# CPLD.net
KiCad netlist of a schematic drawn in Altium Designer
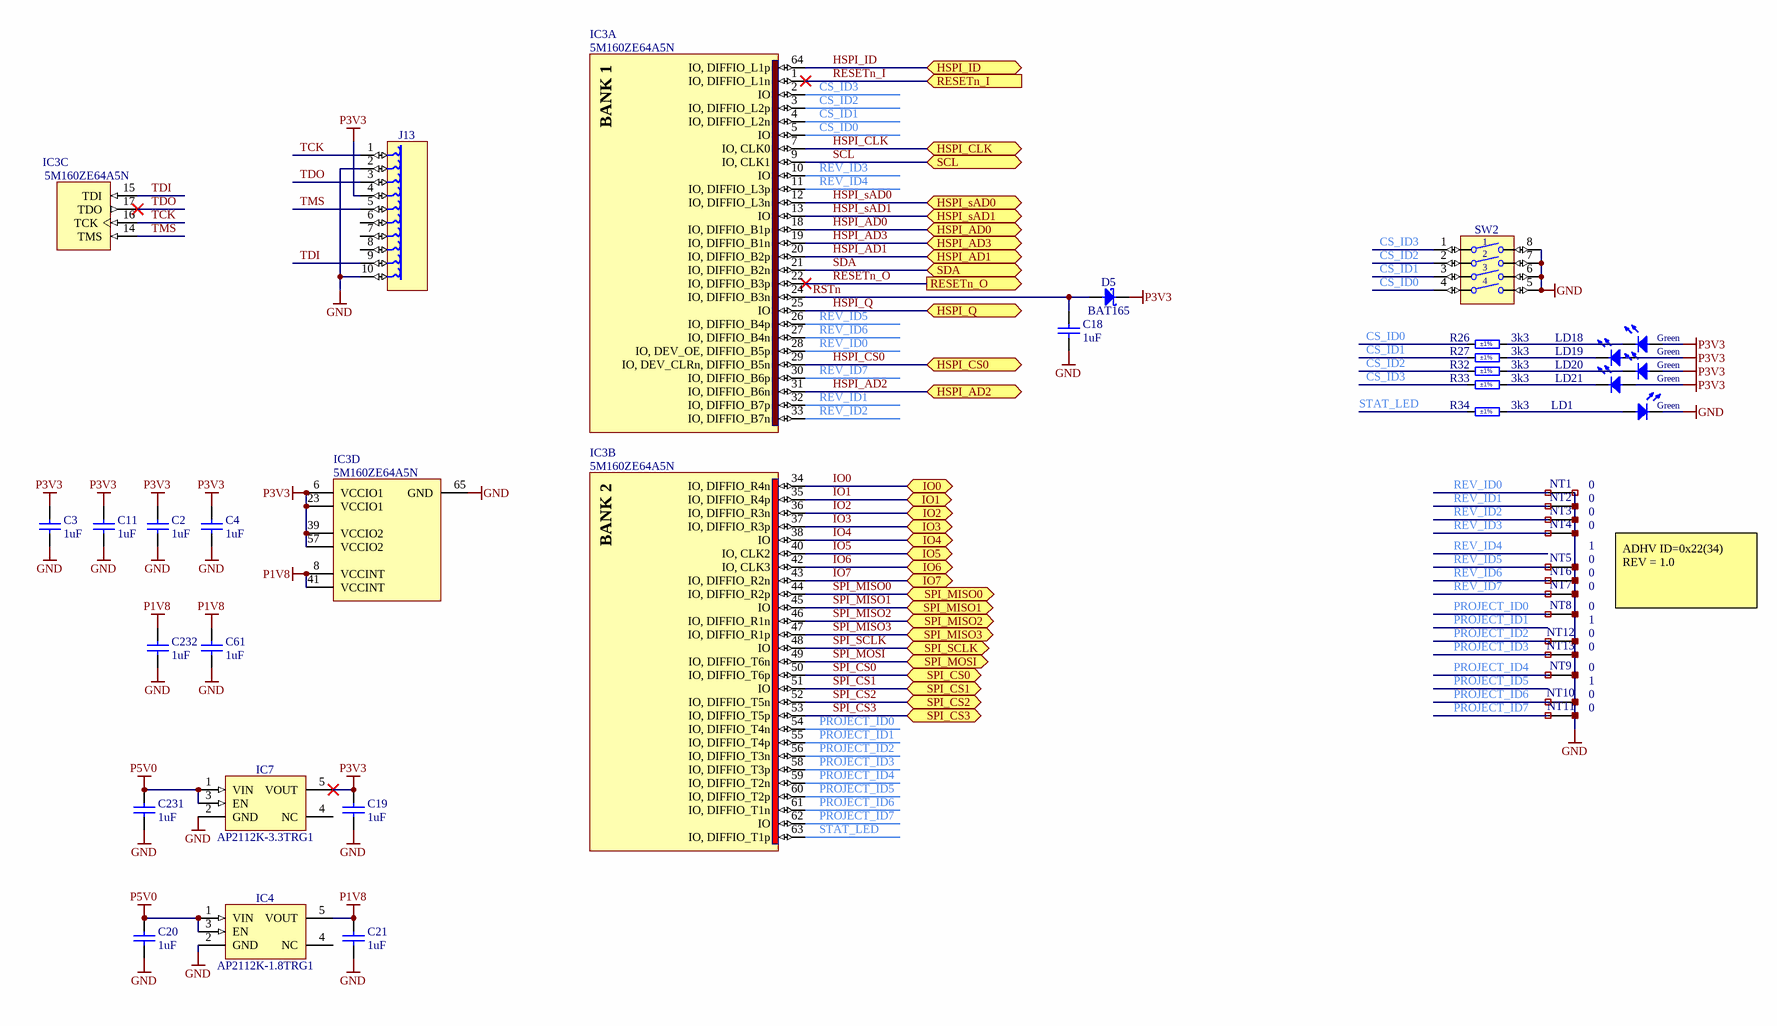
[diagram p0: CPLD.SchDoc]

(export (version "E")
  (design (tool "Eeschema 10.0.6"))
  (components
    (comp (ref "C2")
      (value "1uF")
      (footprint "CAPC1005X55N")
      (description "Non-polarised capacitor")
      (fields
        (field (name "PART NUMBER") "CC0402_1UF_16V_10%_X5R")
        (field (name "VOLTAGE") "16V")
        (field (name "AUTHOR") "CERN DEM JLC")
      )
      (libsource (lib "Capacitors") (part "Capacitor - non polarized"))
    )
    (comp (ref "C3")
      (value "1uF")
      (footprint "CAPC1005X55N")
      (description "Non-polarised capacitor")
      (fields
        (field (name "PART NUMBER") "CC0402_1UF_16V_10%_X5R")
        (field (name "VOLTAGE") "16V")
        (field (name "AUTHOR") "CERN DEM JLC")
      )
      (libsource (lib "Capacitors") (part "Capacitor - non polarized"))
    )
    (comp (ref "C4")
      (value "1uF")
      (footprint "CAPC1005X55N")
      (description "Non-polarised capacitor")
      (fields
        (field (name "PART NUMBER") "CC0402_1UF_16V_10%_X5R")
        (field (name "VOLTAGE") "16V")
        (field (name "AUTHOR") "CERN DEM JLC")
      )
      (libsource (lib "Capacitors") (part "Capacitor - non polarized"))
    )
    (comp (ref "C11")
      (value "1uF")
      (footprint "CAPC1005X55N")
      (description "Non-polarised capacitor")
      (fields
        (field (name "PART NUMBER") "CC0402_1UF_16V_10%_X5R")
        (field (name "VOLTAGE") "16V")
        (field (name "AUTHOR") "CERN DEM JLC")
      )
      (libsource (lib "Capacitors") (part "Capacitor - non polarized"))
    )
    (comp (ref "C18")
      (value "1uF")
      (footprint "CAPC1005X55N")
      (description "Non-polarised capacitor")
      (fields
        (field (name "PART NUMBER") "CC0402_1UF_16V_10%_X5R")
        (field (name "VOLTAGE") "16V")
        (field (name "AUTHOR") "CERN DEM JLC")
      )
      (libsource (lib "Capacitors") (part "Capacitor - non polarized"))
    )
    (comp (ref "C19")
      (value "1uF")
      (footprint "CAPC1005X55N")
      (description "Non-polarised capacitor")
      (fields
        (field (name "PART NUMBER") "CC0402_1UF_16V_10%_X5R")
        (field (name "VOLTAGE") "16V")
        (field (name "AUTHOR") "CERN DEM JLC")
      )
      (libsource (lib "Capacitors") (part "Capacitor - non polarized"))
    )
    (comp (ref "C20")
      (value "1uF")
      (footprint "CAPC1005X55N")
      (description "Non-polarised capacitor")
      (fields
        (field (name "PART NUMBER") "CC0402_1UF_16V_10%_X5R")
        (field (name "VOLTAGE") "16V")
        (field (name "AUTHOR") "CERN DEM JLC")
      )
      (libsource (lib "Capacitors") (part "Capacitor - non polarized"))
    )
    (comp (ref "C21")
      (value "1uF")
      (footprint "CAPC1005X55N")
      (description "Non-polarised capacitor")
      (fields
        (field (name "PART NUMBER") "CC0402_1UF_16V_10%_X5R")
        (field (name "VOLTAGE") "16V")
        (field (name "AUTHOR") "CERN DEM JLC")
      )
      (libsource (lib "Capacitors") (part "Capacitor - non polarized"))
    )
    (comp (ref "C61")
      (value "1uF")
      (footprint "CAPC1005X55N")
      (description "Non-polarised capacitor")
      (fields
        (field (name "PART NUMBER") "CC0402_1UF_16V_10%_X5R")
        (field (name "VOLTAGE") "16V")
        (field (name "AUTHOR") "CERN DEM JLC")
      )
      (libsource (lib "Capacitors") (part "Capacitor - non polarized"))
    )
    (comp (ref "C231")
      (value "1uF")
      (footprint "CAPC1005X55N")
      (description "Non-polarised capacitor")
      (fields
        (field (name "PART NUMBER") "CC0402_1UF_16V_10%_X5R")
        (field (name "VOLTAGE") "16V")
        (field (name "AUTHOR") "CERN DEM JLC")
      )
      (libsource (lib "Capacitors") (part "Capacitor - non polarized"))
    )
    (comp (ref "C232")
      (value "1uF")
      (footprint "CAPC1005X55N")
      (description "Non-polarised capacitor")
      (fields
        (field (name "PART NUMBER") "CC0402_1UF_16V_10%_X5R")
        (field (name "VOLTAGE") "16V")
        (field (name "AUTHOR") "CERN DEM JLC")
      )
      (libsource (lib "Capacitors") (part "Capacitor - non polarized"))
    )
    (comp (ref "D5")
      (value "BAT165")
      (footprint "SOD2512X110N")
      (description "Schottky Diode")
      (fields
        (field (name "VOLTAGE") "40V")
        (field (name "POWER") "750mA")
        (field (name "AUTHOR") "CERN DEM JLC")
      )
      (libsource (lib "ICs And Semiconductors") (part "Diode Schottky"))
    )
    (comp (ref "IC3")
      (value "5M160ZE64A5N")
      (footprint "QFP40P900X900X120-65N-S550")
      (fields (field (name "MANUFACTURER") "ALTERA") (field (name "AUTHOR") "CERN DEM JLC"))
      (libsource (lib "") (part "5M160ZE64A5N_1"))
    )
    (comp (ref "IC4")
      (value "AP2112K-1.8TRG1")
      (footprint "SOT95P285X140-5N")
      (description "600mA CMOS Low Dropout Linear Regulator with Enable")
      (fields
        (field (name "MANUFACTURER") "DIODES INCORPORATED")
        (field (name "MANUFACTURER PART NUMBER") "AP2112K-1.8")
        (field (name "AUTHOR") "CERN DEM JLC")
      )
      (libsource (lib "ICs And Semiconductors") (part "AP2112K"))
    )
    (comp (ref "IC7")
      (value "AP2112K-3.3TRG1")
      (footprint "SOT95P285X140-5N")
      (description "600mA CMOS Low Dropout Linear Regulator with Enable")
      (fields
        (field (name "MANUFACTURER") "DIODES INCORPORATED")
        (field (name "MANUFACTURER PART NUMBER") "AP2112K-3.3")
        (field (name "AUTHOR") "CERN DEM MR")
      )
      (libsource (lib "ICs And Semiconductors") (part "AP2112K"))
    )
    (comp (ref "J13")
      (value "TC2050-IDC")
      (footprint "TC2050-IDC")
      (description "TC2030-MCP and TC2050-IDC Pad Contact")
      (fields (field (name "AUTHOR") "CERN DEM HF"))
      (libsource (lib "Eletro-mechanical") (part "TC2050-IDC"))
    )
    (comp (ref "LD1")
      (value "Green")
      (footprint "LED_KINGBRIGHT_KP-1608CGCK")
      (description "LED Green 1C 2A")
      (fields
        (field (name "PART NUMBER") "LED_KINGBRIGHT_KP-1608CGCK")
        (field (name "MANUFACTURER") "KINGBRIGHT")
        (field (name "AUTHOR") "CERN DEM HF")
      )
      (libsource (lib "ICs And Semiconductors") (part "LED Green 1C 2A"))
    )
    (comp (ref "LD18")
      (value "Green")
      (footprint "LED_KINGBRIGHT_KP-1608CGCK")
      (description "LED Green 1C 2A")
      (fields
        (field (name "PART NUMBER") "LED_KINGBRIGHT_KP-1608CGCK")
        (field (name "MANUFACTURER") "KINGBRIGHT")
        (field (name "AUTHOR") "CERN DEM HF")
      )
      (libsource (lib "ICs And Semiconductors") (part "LED Green 1C 2A"))
    )
    (comp (ref "LD19")
      (value "Green")
      (footprint "LED_KINGBRIGHT_KP-1608CGCK")
      (description "LED Green 1C 2A")
      (fields
        (field (name "PART NUMBER") "LED_KINGBRIGHT_KP-1608CGCK")
        (field (name "MANUFACTURER") "KINGBRIGHT")
        (field (name "AUTHOR") "CERN DEM HF")
      )
      (libsource (lib "ICs And Semiconductors") (part "LED Green 1C 2A"))
    )
    (comp (ref "LD20")
      (value "Green")
      (footprint "LED_KINGBRIGHT_KP-1608CGCK")
      (description "LED Green 1C 2A")
      (fields
        (field (name "PART NUMBER") "LED_KINGBRIGHT_KP-1608CGCK")
        (field (name "MANUFACTURER") "KINGBRIGHT")
        (field (name "AUTHOR") "CERN DEM HF")
      )
      (libsource (lib "ICs And Semiconductors") (part "LED Green 1C 2A"))
    )
    (comp (ref "LD21")
      (value "Green")
      (footprint "LED_KINGBRIGHT_KP-1608CGCK")
      (description "LED Green 1C 2A")
      (fields
        (field (name "PART NUMBER") "LED_KINGBRIGHT_KP-1608CGCK")
        (field (name "MANUFACTURER") "KINGBRIGHT")
        (field (name "AUTHOR") "CERN DEM HF")
      )
      (libsource (lib "ICs And Semiconductors") (part "LED Green 1C 2A"))
    )
    (comp (ref "NT1")
      (value "Net Tie")
      (footprint "Net Tie 3")
      (fields (field (name "PART NUMBER") "Net Tie 3") (field (name "AUTHOR") "CERN DEM HF"))
      (libsource (lib "Eletro-mechanical") (part "Net Tie_a"))
    )
    (comp (ref "NT2")
      (value "Net Tie")
      (footprint "Net Tie 3")
      (fields (field (name "PART NUMBER") "Net Tie 3") (field (name "AUTHOR") "CERN DEM HF"))
      (libsource (lib "Eletro-mechanical") (part "Net Tie_a"))
    )
    (comp (ref "NT3")
      (value "Net Tie")
      (footprint "Net Tie 3")
      (fields (field (name "PART NUMBER") "Net Tie 3") (field (name "AUTHOR") "CERN DEM HF"))
      (libsource (lib "Eletro-mechanical") (part "Net Tie_a"))
    )
    (comp (ref "NT4")
      (value "Net Tie")
      (footprint "Net Tie 3")
      (fields (field (name "PART NUMBER") "Net Tie 3") (field (name "AUTHOR") "CERN DEM HF"))
      (libsource (lib "Eletro-mechanical") (part "Net Tie_a"))
    )
    (comp (ref "NT5")
      (value "Net Tie")
      (footprint "Net Tie 3")
      (fields (field (name "PART NUMBER") "Net Tie 3") (field (name "AUTHOR") "CERN DEM HF"))
      (libsource (lib "Eletro-mechanical") (part "Net Tie_a"))
    )
    (comp (ref "NT6")
      (value "Net Tie")
      (footprint "Net Tie 3")
      (fields (field (name "PART NUMBER") "Net Tie 3") (field (name "AUTHOR") "CERN DEM HF"))
      (libsource (lib "Eletro-mechanical") (part "Net Tie_a"))
    )
    (comp (ref "NT7")
      (value "Net Tie")
      (footprint "Net Tie 3")
      (fields (field (name "PART NUMBER") "Net Tie 3") (field (name "AUTHOR") "CERN DEM HF"))
      (libsource (lib "Eletro-mechanical") (part "Net Tie_a"))
    )
    (comp (ref "NT8")
      (value "Net Tie")
      (footprint "Net Tie 3")
      (fields (field (name "PART NUMBER") "Net Tie 3") (field (name "AUTHOR") "CERN DEM HF"))
      (libsource (lib "Eletro-mechanical") (part "Net Tie_a"))
    )
    (comp (ref "NT9")
      (value "Net Tie")
      (footprint "Net Tie 3")
      (fields (field (name "PART NUMBER") "Net Tie 3") (field (name "AUTHOR") "CERN DEM HF"))
      (libsource (lib "Eletro-mechanical") (part "Net Tie_a"))
    )
    (comp (ref "NT10")
      (value "Net Tie")
      (footprint "Net Tie 3")
      (fields (field (name "PART NUMBER") "Net Tie 3") (field (name "AUTHOR") "CERN DEM HF"))
      (libsource (lib "Eletro-mechanical") (part "Net Tie_a"))
    )
    (comp (ref "NT11")
      (value "Net Tie")
      (footprint "Net Tie 3")
      (fields (field (name "PART NUMBER") "Net Tie 3") (field (name "AUTHOR") "CERN DEM HF"))
      (libsource (lib "Eletro-mechanical") (part "Net Tie_a"))
    )
    (comp (ref "NT12")
      (value "Net Tie")
      (footprint "Net Tie 3")
      (fields (field (name "PART NUMBER") "Net Tie 3") (field (name "AUTHOR") "CERN DEM HF"))
      (libsource (lib "Eletro-mechanical") (part "Net Tie_a"))
    )
    (comp (ref "NT13")
      (value "Net Tie")
      (footprint "Net Tie 3")
      (fields (field (name "PART NUMBER") "Net Tie 3") (field (name "AUTHOR") "CERN DEM HF"))
      (libsource (lib "Eletro-mechanical") (part "Net Tie_a"))
    )
    (comp (ref "R26")
      (value "3k3")
      (footprint "RESC1005X40N")
      (description "Resistor - 1%")
      (fields
        (field (name "TOLERANCE") "±1%")
        (field (name "PART NUMBER") "R0402_3K3_1%_0.0625W_100PPM")
        (field (name "POWER") "0.0625W")
        (field (name "AUTHOR") "CERN DEM JLC")
      )
      (libsource (lib "Resistors") (part "Resistor - 1%"))
    )
    (comp (ref "R27")
      (value "3k3")
      (footprint "RESC1005X40N")
      (description "Resistor - 1%")
      (fields
        (field (name "TOLERANCE") "±1%")
        (field (name "PART NUMBER") "R0402_3K3_1%_0.0625W_100PPM")
        (field (name "POWER") "0.0625W")
        (field (name "AUTHOR") "CERN DEM JLC")
      )
      (libsource (lib "Resistors") (part "Resistor - 1%"))
    )
    (comp (ref "R32")
      (value "3k3")
      (footprint "RESC1005X40N")
      (description "Resistor - 1%")
      (fields
        (field (name "TOLERANCE") "±1%")
        (field (name "PART NUMBER") "R0402_3K3_1%_0.0625W_100PPM")
        (field (name "POWER") "0.0625W")
        (field (name "AUTHOR") "CERN DEM JLC")
      )
      (libsource (lib "Resistors") (part "Resistor - 1%"))
    )
    (comp (ref "R33")
      (value "3k3")
      (footprint "RESC1005X40N")
      (description "Resistor - 1%")
      (fields
        (field (name "TOLERANCE") "±1%")
        (field (name "PART NUMBER") "R0402_3K3_1%_0.0625W_100PPM")
        (field (name "POWER") "0.0625W")
        (field (name "AUTHOR") "CERN DEM JLC")
      )
      (libsource (lib "Resistors") (part "Resistor - 1%"))
    )
    (comp (ref "R34")
      (value "3k3")
      (footprint "RESC1005X40N")
      (description "Resistor - 1%")
      (fields
        (field (name "TOLERANCE") "±1%")
        (field (name "PART NUMBER") "R0402_3K3_1%_0.0625W_100PPM")
        (field (name "POWER") "0.0625W")
        (field (name "AUTHOR") "CERN DEM JLC")
      )
      (libsource (lib "Resistors") (part "Resistor - 1%"))
    )
    (comp (ref "SW2")
      (value "Switch")
      (footprint "SW_OMRON_A6H-4102")
      (description "4 Ways SPST DIP Switch")
      (fields
        (field (name "PART NUMBER") "SW_OMRON_A6H-4102")
        (field (name "MANUFACTURER") "OMRON")
        (field (name "AUTHOR") "CERN DEM JLC")
      )
      (libsource (lib "Eletro-mechanical") (part "SW 4x SPST DIP Switch"))
    )
  )
  (nets
    (net (code "1") (name "/CS_ID0") (class "Default")
      (node (ref "IC3") (pin "5") (pinfunction "IO_5") (pintype "bidirectional"))
      (node (ref "R26") (pin "2") (pinfunction "2_2") (pintype "passive"))
      (node (ref "SW2") (pin "4") (pinfunction "4_4") (pintype "bidirectional"))
    )
    (net (code "2") (name "/CS_ID1") (class "Default")
      (node (ref "IC3") (pin "4") (pinfunction "IO,_DIFFIO_L2n_4") (pintype "bidirectional"))
      (node (ref "R27") (pin "2") (pinfunction "2_2") (pintype "passive"))
      (node (ref "SW2") (pin "3") (pinfunction "3_3") (pintype "bidirectional"))
    )
    (net (code "3") (name "/CS_ID2") (class "Default")
      (node (ref "IC3") (pin "3") (pinfunction "IO,_DIFFIO_L2p_3") (pintype "bidirectional"))
      (node (ref "R32") (pin "2") (pinfunction "2_2") (pintype "passive"))
      (node (ref "SW2") (pin "2") (pinfunction "2_2") (pintype "bidirectional"))
    )
    (net (code "4") (name "/CS_ID3") (class "Default")
      (node (ref "IC3") (pin "2") (pinfunction "IO_2") (pintype "bidirectional"))
      (node (ref "R33") (pin "2") (pinfunction "2_2") (pintype "passive"))
      (node (ref "SW2") (pin "1") (pinfunction "1_1") (pintype "bidirectional"))
    )
    (net (code "5") (name "/HSPI_AD0") (class "Default")
      (node (ref "IC3") (pin "18") (pinfunction "IO,_DIFFIO_B1p_18") (pintype "bidirectional"))
    )
    (net (code "6") (name "/HSPI_AD1") (class "Default")
      (node (ref "IC3") (pin "20") (pinfunction "IO,_DIFFIO_B2p_20") (pintype "bidirectional"))
    )
    (net (code "7") (name "/HSPI_AD2") (class "Default")
      (node (ref "IC3") (pin "31") (pinfunction "IO,_DIFFIO_B6n_31") (pintype "bidirectional"))
    )
    (net (code "8") (name "/HSPI_AD3") (class "Default")
      (node (ref "IC3") (pin "19") (pinfunction "IO,_DIFFIO_B1n_19") (pintype "bidirectional"))
    )
    (net (code "9") (name "/HSPI_CLK") (class "Default")
      (node (ref "IC3") (pin "7") (pinfunction "IO,_CLK0_7") (pintype "bidirectional"))
    )
    (net (code "10") (name "/HSPI_CS0") (class "Default")
      (node (ref "IC3") (pin "29") (pinfunction "IO,_DEV_CLRn,_DIFFIO_B5n_29") (pintype "bidirectional"))
    )
    (net (code "11") (name "/HSPI_ID") (class "Default")
      (node (ref "IC3") (pin "64") (pinfunction "IO,_DIFFIO_L1p_64") (pintype "bidirectional"))
    )
    (net (code "12") (name "/HSPI_Q") (class "Default")
      (node (ref "IC3") (pin "25") (pinfunction "IO_25") (pintype "bidirectional"))
    )
    (net (code "13") (name "/HSPI_sAD0") (class "Default")
      (node (ref "IC3") (pin "12") (pinfunction "IO,_DIFFIO_L3n_12") (pintype "bidirectional"))
    )
    (net (code "14") (name "/HSPI_sAD1") (class "Default")
      (node (ref "IC3") (pin "13") (pinfunction "IO_13") (pintype "bidirectional"))
    )
    (net (code "15") (name "/IO0") (class "Default")
      (node (ref "IC3") (pin "34") (pinfunction "IO,_DIFFIO_R4n_34") (pintype "bidirectional"))
    )
    (net (code "16") (name "/IO1") (class "Default")
      (node (ref "IC3") (pin "35") (pinfunction "IO,_DIFFIO_R4p_35") (pintype "bidirectional"))
    )
    (net (code "17") (name "/IO2") (class "Default")
      (node (ref "IC3") (pin "36") (pinfunction "IO,_DIFFIO_R3n_36") (pintype "bidirectional"))
    )
    (net (code "18") (name "/IO3") (class "Default")
      (node (ref "IC3") (pin "37") (pinfunction "IO,_DIFFIO_R3p_37") (pintype "bidirectional"))
    )
    (net (code "19") (name "/IO4") (class "Default")
      (node (ref "IC3") (pin "38") (pinfunction "IO_38") (pintype "bidirectional"))
    )
    (net (code "20") (name "/IO5") (class "Default")
      (node (ref "IC3") (pin "40") (pinfunction "IO,_CLK2_40") (pintype "bidirectional"))
    )
    (net (code "21") (name "/IO6") (class "Default")
      (node (ref "IC3") (pin "42") (pinfunction "IO,_CLK3_42") (pintype "bidirectional"))
    )
    (net (code "22") (name "/IO7") (class "Default")
      (node (ref "IC3") (pin "43") (pinfunction "IO,_DIFFIO_R2n_43") (pintype "bidirectional"))
    )
    (net (code "23") (name "/PROJECT_ID0") (class "Default")
      (node (ref "IC3") (pin "54") (pinfunction "IO,_DIFFIO_T4n_54") (pintype "bidirectional"))
      (node (ref "NT8") (pin "1") (pinfunction "1_1") (pintype "bidirectional"))
    )
    (net (code "24") (name "/PROJECT_ID1") (class "Default")
      (node (ref "IC3") (pin "55") (pinfunction "IO,_DIFFIO_T4p_55") (pintype "bidirectional"))
    )
    (net (code "25") (name "/PROJECT_ID2") (class "Default")
      (node (ref "IC3") (pin "56") (pinfunction "IO,_DIFFIO_T3n_56") (pintype "bidirectional"))
      (node (ref "NT12") (pin "1") (pinfunction "1_1") (pintype "bidirectional"))
    )
    (net (code "26") (name "/PROJECT_ID3") (class "Default")
      (node (ref "IC3") (pin "58") (pinfunction "IO,_DIFFIO_T3p_58") (pintype "bidirectional"))
      (node (ref "NT13") (pin "1") (pinfunction "1_1") (pintype "bidirectional"))
    )
    (net (code "27") (name "/PROJECT_ID4") (class "Default")
      (node (ref "IC3") (pin "59") (pinfunction "IO,_DIFFIO_T2n_59") (pintype "bidirectional"))
      (node (ref "NT9") (pin "1") (pinfunction "1_1") (pintype "bidirectional"))
    )
    (net (code "28") (name "/PROJECT_ID5") (class "Default")
      (node (ref "IC3") (pin "60") (pinfunction "IO,_DIFFIO_T2p_60") (pintype "bidirectional"))
    )
    (net (code "29") (name "/PROJECT_ID6") (class "Default")
      (node (ref "IC3") (pin "61") (pinfunction "IO,_DIFFIO_T1n_61") (pintype "bidirectional"))
      (node (ref "NT10") (pin "1") (pinfunction "1_1") (pintype "bidirectional"))
    )
    (net (code "30") (name "/PROJECT_ID7") (class "Default")
      (node (ref "IC3") (pin "62") (pinfunction "IO_62") (pintype "bidirectional"))
      (node (ref "NT11") (pin "1") (pinfunction "1_1") (pintype "bidirectional"))
    )
    (net (code "31") (name "/RESETn_I") (class "Default")
      (node (ref "IC3") (pin "1") (pinfunction "IO,_DIFFIO_L1n_1") (pintype "bidirectional+no_connect"))
    )
    (net (code "32") (name "/RESETn_O") (class "Default")
      (node (ref "IC3") (pin "22") (pinfunction "IO,_DIFFIO_B3p_22") (pintype "bidirectional+no_connect"))
    )
    (net (code "33") (name "/REV_ID0") (class "Default")
      (node (ref "IC3") (pin "28") (pinfunction "IO,_DEV_OE,_DIFFIO_B5p_28") (pintype "bidirectional"))
      (node (ref "NT1") (pin "1") (pinfunction "1_1") (pintype "bidirectional"))
    )
    (net (code "34") (name "/REV_ID1") (class "Default")
      (node (ref "IC3") (pin "32") (pinfunction "IO,_DIFFIO_B7p_32") (pintype "bidirectional"))
      (node (ref "NT2") (pin "1") (pinfunction "1_1") (pintype "bidirectional"))
    )
    (net (code "35") (name "/REV_ID2") (class "Default")
      (node (ref "IC3") (pin "33") (pinfunction "IO,_DIFFIO_B7n_33") (pintype "bidirectional"))
      (node (ref "NT3") (pin "1") (pinfunction "1_1") (pintype "bidirectional"))
    )
    (net (code "36") (name "/REV_ID3") (class "Default")
      (node (ref "IC3") (pin "10") (pinfunction "IO_10") (pintype "bidirectional"))
      (node (ref "NT4") (pin "1") (pinfunction "1_1") (pintype "bidirectional"))
    )
    (net (code "37") (name "/REV_ID4") (class "Default")
      (node (ref "IC3") (pin "11") (pinfunction "IO,_DIFFIO_L3p_11") (pintype "bidirectional"))
    )
    (net (code "38") (name "/REV_ID5") (class "Default")
      (node (ref "IC3") (pin "26") (pinfunction "IO,_DIFFIO_B4p_26") (pintype "bidirectional"))
      (node (ref "NT5") (pin "1") (pinfunction "1_1") (pintype "bidirectional"))
    )
    (net (code "39") (name "/REV_ID6") (class "Default")
      (node (ref "IC3") (pin "27") (pinfunction "IO,_DIFFIO_B4n_27") (pintype "bidirectional"))
      (node (ref "NT6") (pin "1") (pinfunction "1_1") (pintype "bidirectional"))
    )
    (net (code "40") (name "/REV_ID7") (class "Default")
      (node (ref "IC3") (pin "30") (pinfunction "IO,_DIFFIO_B6p_30") (pintype "bidirectional"))
      (node (ref "NT7") (pin "1") (pinfunction "1_1") (pintype "bidirectional"))
    )
    (net (code "41") (name "/RSTn") (class "Default")
      (node (ref "C18") (pin "2") (pinfunction "2_2") (pintype "passive"))
      (node (ref "D5") (pin "2") (pinfunction "A_2") (pintype "passive"))
      (node (ref "IC3") (pin "24") (pinfunction "IO,_DIFFIO_B3n_24") (pintype "bidirectional"))
    )
    (net (code "42") (name "/SCL") (class "Default")
      (node (ref "IC3") (pin "9") (pinfunction "IO,_CLK1_9") (pintype "bidirectional"))
    )
    (net (code "43") (name "/SDA") (class "Default")
      (node (ref "IC3") (pin "21") (pinfunction "IO,_DIFFIO_B2n_21") (pintype "bidirectional"))
    )
    (net (code "44") (name "/SPI_CS0") (class "Default")
      (node (ref "IC3") (pin "50") (pinfunction "IO,_DIFFIO_T6p_50") (pintype "bidirectional"))
    )
    (net (code "45") (name "/SPI_CS1") (class "Default")
      (node (ref "IC3") (pin "51") (pinfunction "IO_51") (pintype "bidirectional"))
    )
    (net (code "46") (name "/SPI_CS2") (class "Default")
      (node (ref "IC3") (pin "52") (pinfunction "IO,_DIFFIO_T5n_52") (pintype "bidirectional"))
    )
    (net (code "47") (name "/SPI_CS3") (class "Default")
      (node (ref "IC3") (pin "53") (pinfunction "IO,_DIFFIO_T5p_53") (pintype "bidirectional"))
    )
    (net (code "48") (name "/SPI_MISO0") (class "Default")
      (node (ref "IC3") (pin "44") (pinfunction "IO,_DIFFIO_R2p_44") (pintype "bidirectional"))
    )
    (net (code "49") (name "/SPI_MISO1") (class "Default")
      (node (ref "IC3") (pin "45") (pinfunction "IO_45") (pintype "bidirectional"))
    )
    (net (code "50") (name "/SPI_MISO2") (class "Default")
      (node (ref "IC3") (pin "46") (pinfunction "IO,_DIFFIO_R1n_46") (pintype "bidirectional"))
    )
    (net (code "51") (name "/SPI_MISO3") (class "Default")
      (node (ref "IC3") (pin "47") (pinfunction "IO,_DIFFIO_R1p_47") (pintype "bidirectional"))
    )
    (net (code "52") (name "/SPI_MOSI") (class "Default")
      (node (ref "IC3") (pin "49") (pinfunction "IO,_DIFFIO_T6n_49") (pintype "bidirectional"))
    )
    (net (code "53") (name "/SPI_SCLK") (class "Default")
      (node (ref "IC3") (pin "48") (pinfunction "IO_48") (pintype "bidirectional"))
    )
    (net (code "54") (name "/STAT_LED") (class "Default")
      (node (ref "IC3") (pin "63") (pinfunction "IO,_DIFFIO_T1p_63") (pintype "bidirectional"))
      (node (ref "R34") (pin "2") (pinfunction "2_2") (pintype "passive"))
    )
    (net (code "55") (name "/TCK") (class "Default")
      (node (ref "IC3") (pin "16") (pinfunction "TCK_16") (pintype "input"))
      (node (ref "J13") (pin "1") (pinfunction "1_1") (pintype "bidirectional"))
    )
    (net (code "56") (name "/TDI") (class "Default")
      (node (ref "IC3") (pin "15") (pinfunction "TDI_15") (pintype "input"))
      (node (ref "J13") (pin "9") (pinfunction "9_9") (pintype "bidirectional"))
    )
    (net (code "57") (name "/TDO") (class "Default")
      (node (ref "IC3") (pin "17") (pinfunction "TDO_17") (pintype "output"))
      (node (ref "J13") (pin "3") (pinfunction "3_3") (pintype "bidirectional"))
    )
    (net (code "58") (name "/TMS") (class "Default")
      (node (ref "IC3") (pin "14") (pinfunction "TMS_14") (pintype "input"))
      (node (ref "J13") (pin "5") (pinfunction "5_5") (pintype "bidirectional"))
    )
    (net (code "59") (name "GND") (class "Default")
      (node (ref "C11") (pin "1") (pinfunction "1_1") (pintype "passive"))
      (node (ref "C18") (pin "1") (pinfunction "1_1") (pintype "passive"))
      (node (ref "C19") (pin "1") (pinfunction "1_1") (pintype "passive"))
      (node (ref "C2") (pin "1") (pinfunction "1_1") (pintype "passive"))
      (node (ref "C20") (pin "1") (pinfunction "1_1") (pintype "passive"))
      (node (ref "C21") (pin "1") (pinfunction "1_1") (pintype "passive"))
      (node (ref "C231") (pin "1") (pinfunction "1_1") (pintype "passive"))
      (node (ref "C232") (pin "1") (pinfunction "1_1") (pintype "passive"))
      (node (ref "C3") (pin "1") (pinfunction "1_1") (pintype "passive"))
      (node (ref "C4") (pin "1") (pinfunction "1_1") (pintype "passive"))
      (node (ref "C61") (pin "1") (pinfunction "1_1") (pintype "passive"))
      (node (ref "IC3") (pin "65") (pinfunction "GND_65") (pintype "power_in"))
      (node (ref "IC4") (pin "2") (pinfunction "GND_2") (pintype "power_in"))
      (node (ref "IC7") (pin "2") (pinfunction "GND_2") (pintype "power_in"))
      (node (ref "J13") (pin "10") (pinfunction "10_10") (pintype "bidirectional"))
      (node (ref "J13") (pin "2") (pinfunction "2_2") (pintype "bidirectional"))
      (node (ref "LD1") (pin "1") (pinfunction "C_1") (pintype "passive"))
      (node (ref "NT1") (pin "2") (pinfunction "2_2") (pintype "bidirectional"))
      (node (ref "NT10") (pin "2") (pinfunction "2_2") (pintype "bidirectional"))
      (node (ref "NT11") (pin "2") (pinfunction "2_2") (pintype "bidirectional"))
      (node (ref "NT12") (pin "2") (pinfunction "2_2") (pintype "bidirectional"))
      (node (ref "NT13") (pin "2") (pinfunction "2_2") (pintype "bidirectional"))
      (node (ref "NT2") (pin "2") (pinfunction "2_2") (pintype "bidirectional"))
      (node (ref "NT3") (pin "2") (pinfunction "2_2") (pintype "bidirectional"))
      (node (ref "NT4") (pin "2") (pinfunction "2_2") (pintype "bidirectional"))
      (node (ref "NT5") (pin "2") (pinfunction "2_2") (pintype "bidirectional"))
      (node (ref "NT6") (pin "2") (pinfunction "2_2") (pintype "bidirectional"))
      (node (ref "NT7") (pin "2") (pinfunction "2_2") (pintype "bidirectional"))
      (node (ref "NT8") (pin "2") (pinfunction "2_2") (pintype "bidirectional"))
      (node (ref "NT9") (pin "2") (pinfunction "2_2") (pintype "bidirectional"))
      (node (ref "SW2") (pin "5") (pinfunction "5_5") (pintype "bidirectional"))
      (node (ref "SW2") (pin "6") (pinfunction "6_6") (pintype "bidirectional"))
      (node (ref "SW2") (pin "7") (pinfunction "7_7") (pintype "bidirectional"))
      (node (ref "SW2") (pin "8") (pinfunction "8_8") (pintype "bidirectional"))
    )
    (net (code "60") (name "Net-(LD1-A)") (class "Default")
      (node (ref "LD1") (pin "2") (pinfunction "A_2") (pintype "passive"))
      (node (ref "R34") (pin "1") (pinfunction "1_1") (pintype "passive"))
    )
    (net (code "61") (name "Net-(LD18-C)") (class "Default")
      (node (ref "LD18") (pin "1") (pinfunction "C_1") (pintype "passive"))
      (node (ref "R26") (pin "1") (pinfunction "1_1") (pintype "passive"))
    )
    (net (code "62") (name "Net-(LD19-C)") (class "Default")
      (node (ref "LD19") (pin "1") (pinfunction "C_1") (pintype "passive"))
      (node (ref "R27") (pin "1") (pinfunction "1_1") (pintype "passive"))
    )
    (net (code "63") (name "Net-(LD20-C)") (class "Default")
      (node (ref "LD20") (pin "1") (pinfunction "C_1") (pintype "passive"))
      (node (ref "R32") (pin "1") (pinfunction "1_1") (pintype "passive"))
    )
    (net (code "64") (name "Net-(LD21-C)") (class "Default")
      (node (ref "LD21") (pin "1") (pinfunction "C_1") (pintype "passive"))
      (node (ref "R33") (pin "1") (pinfunction "1_1") (pintype "passive"))
    )
    (net (code "65") (name "P1V8") (class "Default")
      (node (ref "C21") (pin "2") (pinfunction "2_2") (pintype "passive"))
      (node (ref "C232") (pin "2") (pinfunction "2_2") (pintype "passive"))
      (node (ref "C61") (pin "2") (pinfunction "2_2") (pintype "passive"))
      (node (ref "IC3") (pin "41") (pinfunction "VCCINT_41") (pintype "power_in"))
      (node (ref "IC3") (pin "8") (pinfunction "VCCINT_8") (pintype "power_in"))
      (node (ref "IC4") (pin "5") (pinfunction "VOUT_5") (pintype "power_in"))
    )
    (net (code "66") (name "P3V3") (class "Default")
      (node (ref "C11") (pin "2") (pinfunction "2_2") (pintype "passive"))
      (node (ref "C19") (pin "2") (pinfunction "2_2") (pintype "passive"))
      (node (ref "C2") (pin "2") (pinfunction "2_2") (pintype "passive"))
      (node (ref "C3") (pin "2") (pinfunction "2_2") (pintype "passive"))
      (node (ref "C4") (pin "2") (pinfunction "2_2") (pintype "passive"))
      (node (ref "D5") (pin "1") (pinfunction "C_1") (pintype "passive"))
      (node (ref "IC3") (pin "23") (pinfunction "VCCIO1_23") (pintype "power_in"))
      (node (ref "IC3") (pin "39") (pinfunction "VCCIO2_39") (pintype "power_in"))
      (node (ref "IC3") (pin "57") (pinfunction "VCCIO2_57") (pintype "power_in"))
      (node (ref "IC3") (pin "6") (pinfunction "VCCIO1_6") (pintype "power_in"))
      (node (ref "IC7") (pin "5") (pinfunction "VOUT_5") (pintype "power_in"))
      (node (ref "J13") (pin "4") (pinfunction "4_4") (pintype "bidirectional"))
      (node (ref "LD18") (pin "2") (pinfunction "A_2") (pintype "passive"))
      (node (ref "LD19") (pin "2") (pinfunction "A_2") (pintype "passive"))
      (node (ref "LD20") (pin "2") (pinfunction "A_2") (pintype "passive"))
      (node (ref "LD21") (pin "2") (pinfunction "A_2") (pintype "passive"))
    )
    (net (code "67") (name "P5V0") (class "Default")
      (node (ref "C20") (pin "2") (pinfunction "2_2") (pintype "passive"))
      (node (ref "C231") (pin "2") (pinfunction "2_2") (pintype "passive"))
      (node (ref "IC4") (pin "1") (pinfunction "VIN_1") (pintype "input"))
      (node (ref "IC4") (pin "3") (pinfunction "EN_3") (pintype "input"))
      (node (ref "IC7") (pin "1") (pinfunction "VIN_1") (pintype "input"))
      (node (ref "IC7") (pin "3") (pinfunction "EN_3") (pintype "input"))
    )
    (net (code "68") (name "unconnected-(IC4-NC-Pad4)") (class "Default")
      (node (ref "IC4") (pin "4") (pinfunction "NC_4") (pintype "passive"))
    )
    (net (code "69") (name "unconnected-(IC7-NC-Pad4)") (class "Default")
      (node (ref "IC7") (pin "4") (pinfunction "NC_4") (pintype "passive"))
    )
    (net (code "70") (name "unconnected-(J13-Pad6)") (class "Default")
      (node (ref "J13") (pin "6") (pinfunction "6_6") (pintype "bidirectional"))
    )
    (net (code "71") (name "unconnected-(J13-Pad7)") (class "Default")
      (node (ref "J13") (pin "7") (pinfunction "7_7") (pintype "bidirectional"))
    )
    (net (code "72") (name "unconnected-(J13-Pad8)") (class "Default")
      (node (ref "J13") (pin "8") (pinfunction "8_8") (pintype "bidirectional"))
    )
  )
)
